# AD9363_OSCILLATORS.net
KiCad netlist of a schematic drawn in Altium Designer
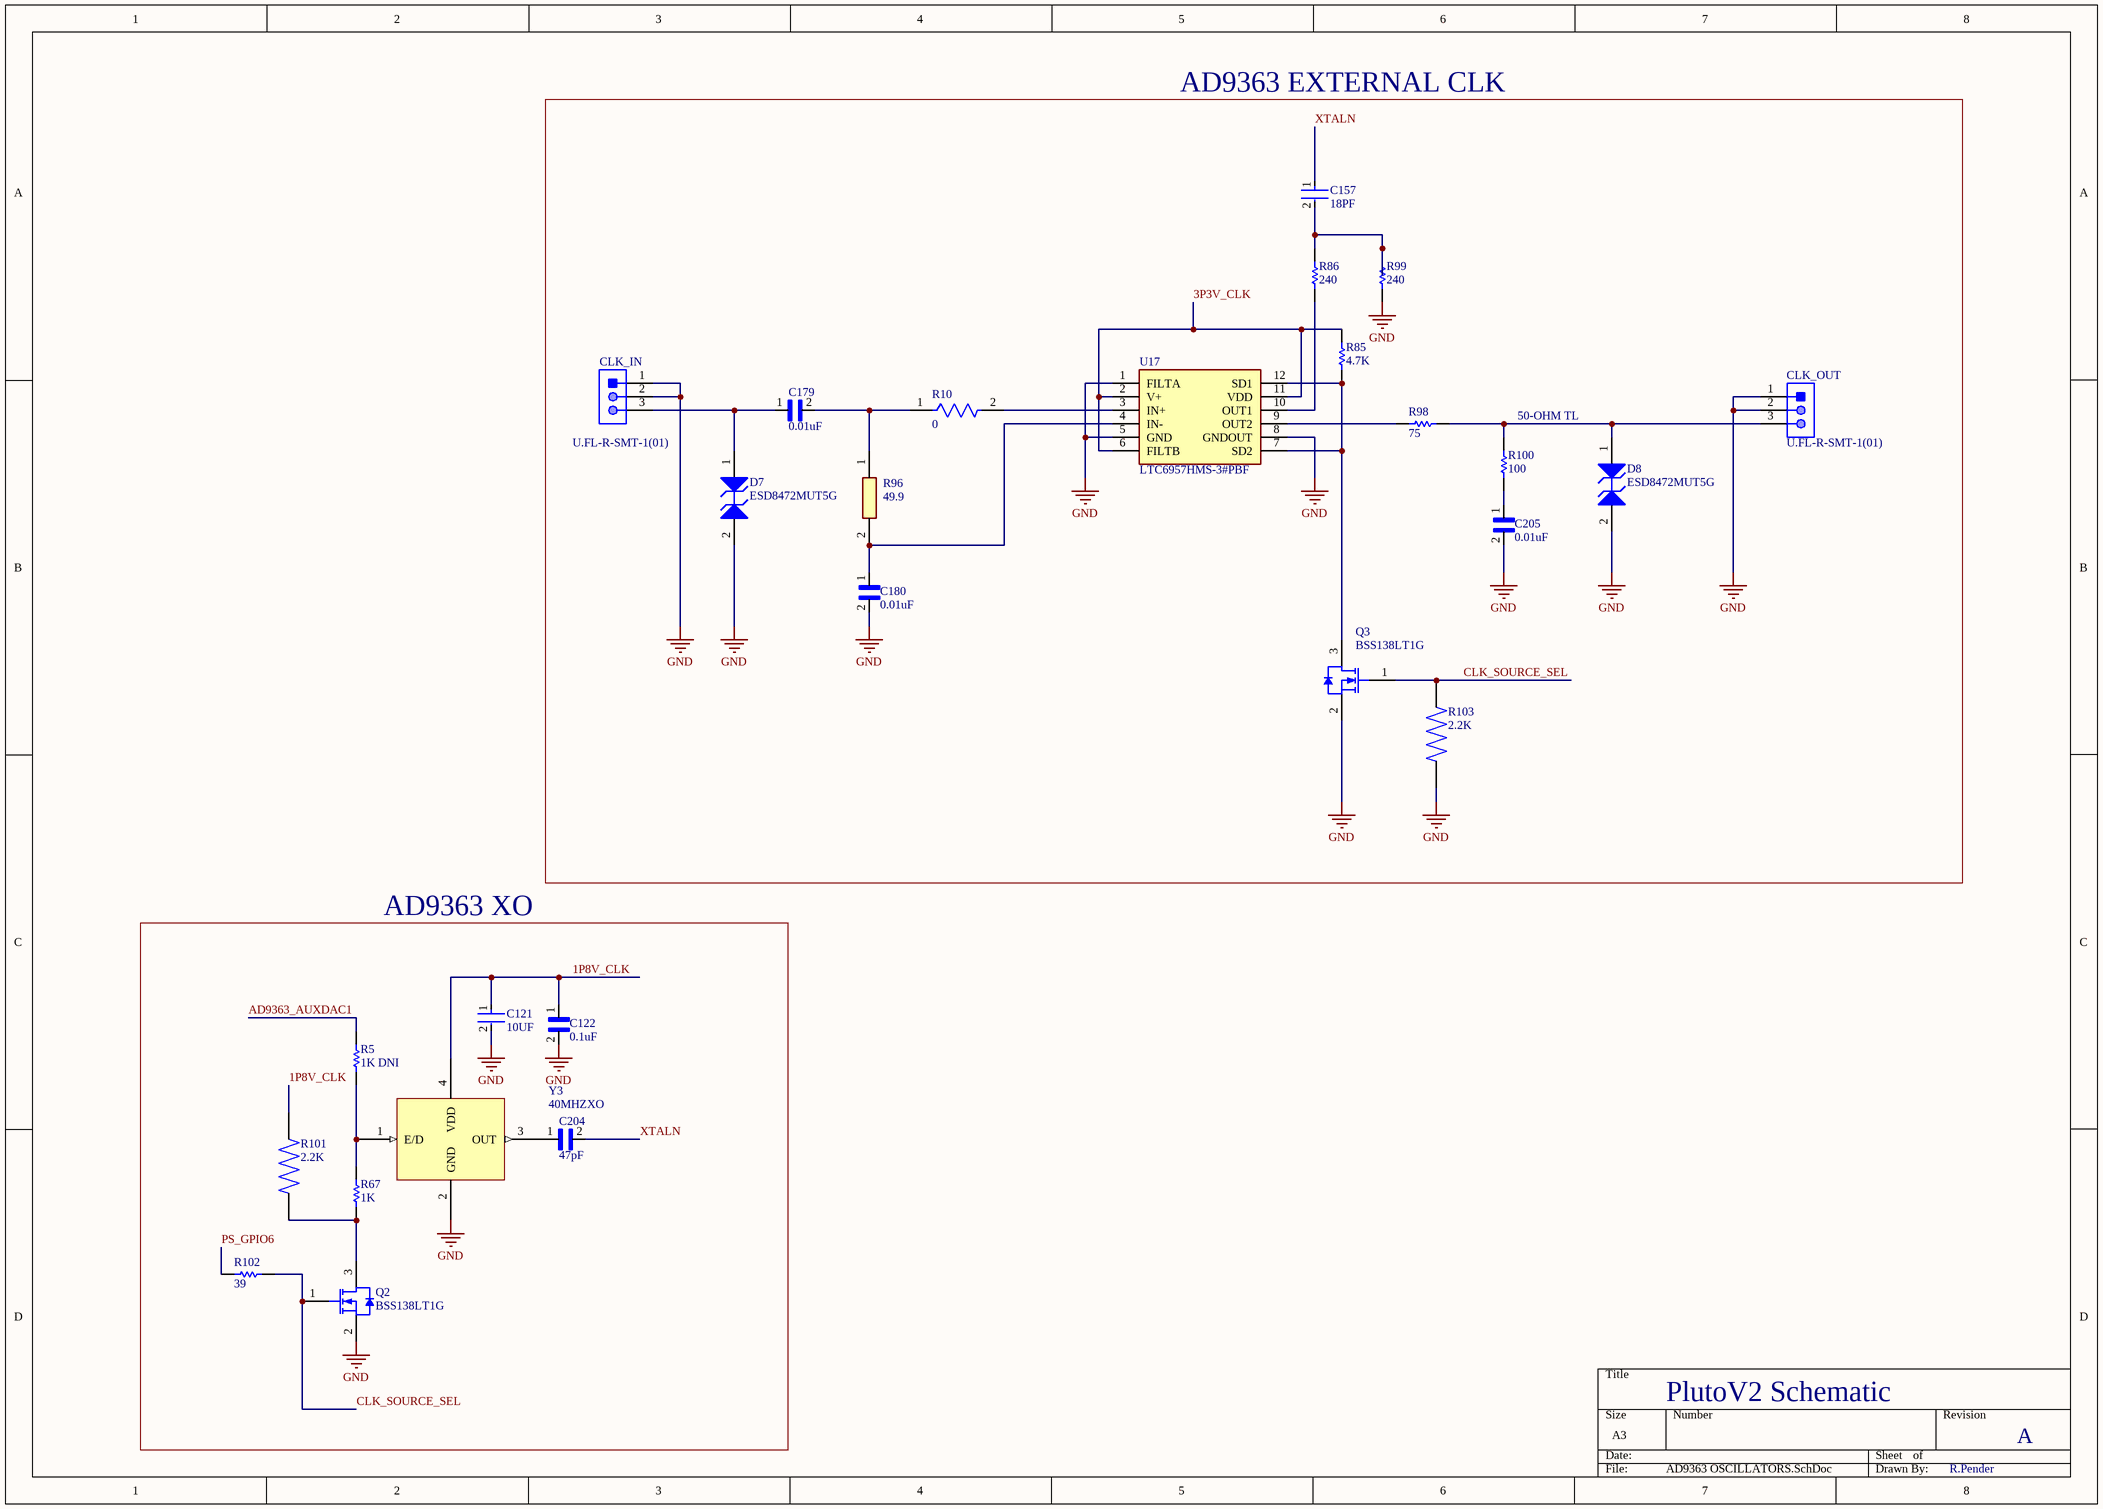
[diagram p0: AD9363 OSCILLATORS.SchDoc]

(export (version "E")
  (design (tool "Eeschema 10.0.6"))
  (components
    (comp (ref "C121")
      (value "10UF")
      (footprint "FP-GRM188-0_1-e0_2_0_55-IPC_A")
      (description "Chip Multilayer Ceramic Capacitors for General Purpose, 0603, 10uF, X5R, 15%, 20%, 6.3V")
      (fields (field (name "VOLTAGE") "6.3V") (field (name "TOLERANCE") "20%"))
      (libsource (lib "Altium Content Vault") (part "02cd4be3c70576c341d710602a673aa"))
    )
    (comp (ref "C122")
      (value "0.1uF")
      (footprint "CAPC0603X33N")
      (description "CAP 0.1UF 16VDC X5R 20% SMD 0201 PAPER TAPE")
      (fields (field (name "MP") "GRM033R61C104ME84D"))
      (libsource (lib "GRM033R61C104ME84D") (part "GRM033R61C104ME84D"))
    )
    (comp (ref "C157")
      (value "18PF")
      (footprint "FP-GRM033-0_03-IPC_A")
      (description "Chip Multilayer Ceramic Capacitors for General Purpose, 0201, 18pF, C0G, 30ppm/°C, 5%, 50V")
      (fields (field (name "TOLERANCE") "5%") (field (name "VOLTAGE") "50V"))
      (libsource (lib "Altium Content Vault") (part "b4654b650e69147ec39a6b967a45e02"))
    )
    (comp (ref "C179")
      (value "0.01uF")
      (footprint "CAPC0603X33N")
      (description "SMD Capacitor X7R(EIA) with Capacitance: 10000pF Tol. 10%. Rated Voltage: 10Vdc")
      (fields (field (name "MP") "GRM033R71A103KA01D") (field (name "MF") "Murata"))
      (libsource (lib "GRM033R71A103KA01D") (part "GRM033R71A103KA01D"))
    )
    (comp (ref "C180")
      (value "0.01uF")
      (footprint "CAPC0603X33N")
      (description "SMD Capacitor X7R(EIA) with Capacitance: 10000pF Tol. 10%. Rated Voltage: 10Vdc")
      (fields (field (name "MP") "GRM033R71A103KA01D") (field (name "MF") "Murata"))
      (libsource (lib "") (part "GRM033R71A103KA01D_1"))
    )
    (comp (ref "C204")
      (value "47pF")
      (footprint "CAPC1005X55N")
      (description "47pF Â±5% 50V Ceramic Capacitor C0G, NP0 0402 (1005 Metric)")
      (fields (field (name "MP") "GCM1555C1H470JA16D") (field (name "MF") "Murata"))
      (libsource (lib "GCM1555C1H470JA16D") (part "GCM1555C1H470JA16D"))
    )
    (comp (ref "C205")
      (value "0.01uF")
      (footprint "CAPC0603X33N")
      (description "SMD Capacitor X7R(EIA) with Capacitance: 10000pF Tol. 10%. Rated Voltage: 10Vdc")
      (fields (field (name "MP") "GRM033R71A103KA01D") (field (name "MF") "Murata"))
      (libsource (lib "") (part "GRM033R71A103KA01D_1"))
    )
    (comp (ref "CLK_IN")
      (value "U.FL-R-SMT-1(01)")
      (footprint "HRS-U.FL-R-SMT-3_V")
      (description "Ultra Small Coaxial Connector, 6 GHz, -40 to 90 degC, 3-Pin SMD, RoHS, Bulk")
      (fields (field (name "MANUFACTURER") "Hirose Electric"))
      (libsource (lib "") (part "CN-1P-M-R3_1"))
    )
    (comp (ref "CLK_OUT")
      (value "U.FL-R-SMT-1(01)")
      (footprint "HRS-U.FL-R-SMT-3_V")
      (description "Ultra Small Coaxial Connector, 6 GHz, -40 to 90 degC, 3-Pin SMD, RoHS, Bulk")
      (fields (field (name "MANUFACTURER") "Hirose Electric"))
      (libsource (lib "Altium Content Vault") (part "CN-1P-M-R3"))
    )
    (comp (ref "D7")
      (value "ESD8472MUT5G")
      (footprint "ONSC-X3DFN-2-152AF-01_V")
      (fields (field (name "MANUFACTURER") "On Semiconductor"))
      (libsource (lib "Altium Content Vault") (part "ONSC-A1A2-2"))
    )
    (comp (ref "D8")
      (value "ESD8472MUT5G")
      (footprint "ONSC-X3DFN-2-152AF-01_V")
      (fields (field (name "MANUFACTURER") "On Semiconductor"))
      (libsource (lib "Altium Content Vault") (part "ONSC-A1A2-2"))
    )
    (comp (ref "Q2")
      (value "BSS138LT1G")
      (footprint "ONSC-SOT-23-3-318-08_V")
      (description "Power MOSFET, 200 mA, 50 V, N-Channel, 3-Pin SOT-23, Pb-Free, Tape and Reel")
      (fields (field (name "MANUFACTURER") "On Semiconductor"))
      (libsource (lib "Altium Content Vault") (part "ONSC-NMOS-G1S2D3-3"))
    )
    (comp (ref "Q3")
      (value "BSS138LT1G")
      (footprint "ONSC-SOT-23-3-318-08_V")
      (description "Power MOSFET, 200 mA, 50 V, N-Channel, 3-Pin SOT-23, Pb-Free, Tape and Reel")
      (fields (field (name "MANUFACTURER") "On Semiconductor"))
      (libsource (lib "Altium Content Vault") (part "ONSC-NMOS-G1S2D3-3"))
    )
    (comp (ref "R5")
      (value "1K DNI")
      (footprint "RESC0603X26X15LL03T05")
      (fields (field (name "MANUFACTURER") "Panasonic") (field (name "PART NUMBER") "ERJ1GNF10R0C"))
      (libsource (lib "Altium Content Vault") (part "RES"))
    )
    (comp (ref "R10")
      (value "0")
      (footprint "FP-ERJ1GN-IPC_A")
      (description "RES SMD 0 OHM JUMPER 1/20W 0201")
      (fields (field (name "TOLERANCE") "1%"))
      (libsource (lib "Altium Content Vault") (part "1029c3af85768c4190bb7ad29bc67b5"))
    )
    (comp (ref "R67")
      (value "1K")
      (footprint "2-0402")
      (fields (field (name "PUBLISHER") "Altium Limited"))
      (libsource (lib "Panasonic Resistor") (part "ERJ2RK"))
    )
    (comp (ref "R85")
      (value "4.7K")
      (footprint "2-0402")
      (fields (field (name "PUBLISHER") "Altium Limited"))
      (libsource (lib "Panasonic Resistor") (part "ERJ2RK"))
    )
    (comp (ref "R86")
      (value "240")
      (footprint "2-0402")
      (fields (field (name "PUBLISHER") "Altium Limited"))
      (libsource (lib "Panasonic Resistor") (part "ERJ2RK"))
    )
    (comp (ref "R96")
      (value "49.9")
      (footprint "SamacSys:RESC1608X46N")
      (description "Resistor")
      (fields (field (name "MANUFACTURER_PART_NUMBER") "PCAN0603E49R9BST5"))
      (libsource (lib "SamacSys") (part "PCAN0603E49R9BST5"))
    )
    (comp (ref "R98")
      (value "75")
      (footprint "2-0402")
      (fields (field (name "PUBLISHER") "Altium Limited"))
      (libsource (lib "Panasonic Resistor") (part "ERJ2RK"))
    )
    (comp (ref "R99")
      (value "240")
      (footprint "2-0402")
      (fields (field (name "PUBLISHER") "Altium Limited"))
      (libsource (lib "Panasonic Resistor") (part "ERJ2RK"))
    )
    (comp (ref "R100")
      (value "100")
      (footprint "2-0402")
      (fields (field (name "PUBLISHER") "Altium Limited"))
      (libsource (lib "Panasonic Resistor") (part "ERJ2RK"))
    )
    (comp (ref "R101")
      (value "2.2K")
      (footprint "RESC1005X35N")
      (description "2.2 kOhms Â±1% 0.063W, 1/16W Chip Resistor 0402 _1005 Metric_ Thick Film")
      (fields (field (name "MF") "Vishay") (field (name "MP") "CRCW04022K20FKEDC"))
      (libsource (lib "CRCW04022K20FKEDC") (part "CRCW04022K20FKEDC"))
    )
    (comp (ref "R102")
      (value "39")
      (footprint "2-0402")
      (description "Thick Film Chip Resistor, 1 Ohm to 2.2M Ohm Range, 5% Tolerance, 0402 Size, 0.063 W")
      (fields (field (name "PUBLISHER") "Altium Limited"))
      (libsource (lib "Panasonic Resistor") (part "ERJ2GE"))
    )
    (comp (ref "R103")
      (value "2.2K")
      (footprint "RESC1005X35N")
      (description "2.2 kOhms Â±1% 0.063W, 1/16W Chip Resistor 0402 _1005 Metric_ Thick Film")
      (fields (field (name "MF") "Vishay") (field (name "MP") "CRCW04022K20FKEDC"))
      (libsource (lib "CRCW04022K20FKEDC") (part "CRCW04022K20FKEDC"))
    )
    (comp (ref "U17")
      (value "LTC6957HMS-3#PBF")
      (footprint "SamacSys:SOP65P490X110-12N")
      (description "Integrated Circuit")
      (fields (field (name "MOUSER2 PART NUMBER") "584-LTC6957HMS-3#PBF"))
      (libsource (lib "SamacSys") (part "LTC6957HMS-3#PBF"))
    )
    (comp (ref "Y3")
      (value "40MHZXO")
      (footprint "XO40MHz2")
      (libsource (lib "RINALDOSCHEMS") (part "40MHZXO"))
    )
  )
  (nets
    (net (code "1") (name "/1P8V_CLK") (class "Default")
      (node (ref "C121") (pin "1") (pinfunction "1_1") (pintype "passive"))
      (node (ref "C122") (pin "1") (pinfunction "1_1") (pintype "passive"))
      (node (ref "R101") (pin "2") (pinfunction "2_2") (pintype "passive"))
      (node (ref "Y3") (pin "4") (pinfunction "VDD_4") (pintype "passive"))
    )
    (net (code "2") (name "/3P3V_CLK") (class "Default")
      (node (ref "R85") (pin "2") (pinfunction "2_2") (pintype "passive"))
      (node (ref "U17") (pin "11") (pinfunction "VDD_11") (pintype "passive"))
      (node (ref "U17") (pin "2") (pinfunction "V+_2") (pintype "passive"))
      (node (ref "U17") (pin "6") (pinfunction "FILTB_6") (pintype "passive"))
    )
    (net (code "3") (name "/AD9363_AUXDAC1") (class "Default")
      (node (ref "R5") (pin "1") (pinfunction "1_1") (pintype "passive"))
    )
    (net (code "4") (name "/CLK_SOURCE_SEL") (class "Default")
      (node (ref "Q2") (pin "1") (pinfunction "G_1") (pintype "passive"))
      (node (ref "Q3") (pin "1") (pinfunction "G_1") (pintype "passive"))
      (node (ref "R102") (pin "2") (pinfunction "2_2") (pintype "passive"))
      (node (ref "R103") (pin "1") (pinfunction "1_1") (pintype "passive"))
    )
    (net (code "5") (name "/PS_GPIO6") (class "Default")
      (node (ref "R102") (pin "1") (pinfunction "1_1") (pintype "passive"))
    )
    (net (code "6") (name "/XTALN") (class "Default")
      (node (ref "C157") (pin "1") (pinfunction "1_1") (pintype "passive"))
      (node (ref "C204") (pin "2") (pinfunction "2_2") (pintype "passive"))
    )
    (net (code "7") (name "GND") (class "Default")
      (node (ref "C121") (pin "2") (pinfunction "2_2") (pintype "passive"))
      (node (ref "C122") (pin "2") (pinfunction "2_2") (pintype "passive"))
      (node (ref "C180") (pin "2") (pinfunction "2_2") (pintype "passive"))
      (node (ref "C205") (pin "2") (pinfunction "2_2") (pintype "passive"))
      (node (ref "CLK_IN") (pin "1") (pinfunction "1_1") (pintype "passive"))
      (node (ref "CLK_IN") (pin "2") (pinfunction "2_2") (pintype "passive"))
      (node (ref "CLK_OUT") (pin "1") (pinfunction "1_1") (pintype "passive"))
      (node (ref "CLK_OUT") (pin "2") (pinfunction "2_2") (pintype "passive"))
      (node (ref "D7") (pin "2") (pinfunction "A2_2") (pintype "passive"))
      (node (ref "D8") (pin "2") (pinfunction "A2_2") (pintype "passive"))
      (node (ref "Q2") (pin "2") (pinfunction "S_2") (pintype "passive"))
      (node (ref "Q3") (pin "2") (pinfunction "S_2") (pintype "passive"))
      (node (ref "R103") (pin "2") (pinfunction "2_2") (pintype "passive"))
      (node (ref "R99") (pin "1") (pinfunction "1_1") (pintype "passive"))
      (node (ref "U17") (pin "1") (pinfunction "FILTA_1") (pintype "passive"))
      (node (ref "U17") (pin "5") (pinfunction "GND_5") (pintype "passive"))
      (node (ref "U17") (pin "8") (pinfunction "GNDOUT_8") (pintype "passive"))
      (node (ref "Y3") (pin "2") (pinfunction "GND_2") (pintype "power_in"))
    )
    (net (code "8") (name "Net-(C157-Pad2)") (class "Default")
      (node (ref "C157") (pin "2") (pinfunction "2_2") (pintype "passive"))
      (node (ref "R86") (pin "2") (pinfunction "2_2") (pintype "passive"))
      (node (ref "R99") (pin "2") (pinfunction "2_2") (pintype "passive"))
    )
    (net (code "9") (name "Net-(C179-Pad2)") (class "Default")
      (node (ref "C179") (pin "2") (pinfunction "2_2") (pintype "passive"))
      (node (ref "R10") (pin "1") (pinfunction "1_1") (pintype "passive"))
      (node (ref "R96") (pin "1") (pinfunction "1_1") (pintype "passive"))
    )
    (net (code "10") (name "Net-(C205-Pad1)") (class "Default")
      (node (ref "C205") (pin "1") (pinfunction "1_1") (pintype "passive"))
      (node (ref "R100") (pin "2") (pinfunction "2_2") (pintype "passive"))
    )
    (net (code "11") (name "Net-(D7-A1)") (class "Default")
      (node (ref "C179") (pin "1") (pinfunction "1_1") (pintype "passive"))
      (node (ref "CLK_IN") (pin "3") (pinfunction "3_3") (pintype "passive"))
      (node (ref "D7") (pin "1") (pinfunction "A1_1") (pintype "passive"))
    )
    (net (code "12") (name "Net-(D8-A1)") (class "Default")
      (node (ref "CLK_OUT") (pin "3") (pinfunction "3_3") (pintype "passive"))
      (node (ref "D8") (pin "1") (pinfunction "A1_1") (pintype "passive"))
      (node (ref "R100") (pin "1") (pinfunction "1_1") (pintype "passive"))
      (node (ref "R98") (pin "2") (pinfunction "2_2") (pintype "passive"))
    )
    (net (code "13") (name "Net-(Q2-D)") (class "Default")
      (node (ref "Q2") (pin "3") (pinfunction "D_3") (pintype "passive"))
      (node (ref "R101") (pin "1") (pinfunction "1_1") (pintype "passive"))
      (node (ref "R67") (pin "2") (pinfunction "2_2") (pintype "passive"))
    )
    (net (code "14") (name "Net-(Q3-D)") (class "Default")
      (node (ref "Q3") (pin "3") (pinfunction "D_3") (pintype "passive"))
      (node (ref "R85") (pin "1") (pinfunction "1_1") (pintype "passive"))
      (node (ref "U17") (pin "12") (pinfunction "SD1_12") (pintype "passive"))
      (node (ref "U17") (pin "7") (pinfunction "SD2_7") (pintype "passive"))
    )
    (net (code "15") (name "Net-(U17-IN+)") (class "Default")
      (node (ref "R10") (pin "2") (pinfunction "2_2") (pintype "passive"))
      (node (ref "U17") (pin "3") (pinfunction "IN+_3") (pintype "passive"))
    )
    (net (code "16") (name "Net-(U17-IN-)") (class "Default")
      (node (ref "C180") (pin "1") (pinfunction "1_1") (pintype "passive"))
      (node (ref "R96") (pin "2") (pinfunction "2_2") (pintype "passive"))
      (node (ref "U17") (pin "4") (pinfunction "IN-_4") (pintype "passive"))
    )
    (net (code "17") (name "Net-(U17-OUT1)") (class "Default")
      (node (ref "R86") (pin "1") (pinfunction "1_1") (pintype "passive"))
      (node (ref "U17") (pin "10") (pinfunction "OUT1_10") (pintype "passive"))
    )
    (net (code "18") (name "Net-(U17-OUT2)") (class "Default")
      (node (ref "R98") (pin "1") (pinfunction "1_1") (pintype "passive"))
      (node (ref "U17") (pin "9") (pinfunction "OUT2_9") (pintype "passive"))
    )
    (net (code "19") (name "Net-(Y3-E{slash}D)") (class "Default")
      (node (ref "R5") (pin "2") (pinfunction "2_2") (pintype "passive"))
      (node (ref "R67") (pin "1") (pinfunction "1_1") (pintype "passive"))
      (node (ref "Y3") (pin "1") (pinfunction "E/D_1") (pintype "input"))
    )
    (net (code "20") (name "Net-(Y3-OUT)") (class "Default")
      (node (ref "C204") (pin "1") (pinfunction "1_1") (pintype "passive"))
      (node (ref "Y3") (pin "3") (pinfunction "OUT_3") (pintype "output"))
    )
  )
)
